# Clocking.net
KiCad netlist of a schematic drawn in Altium Designer
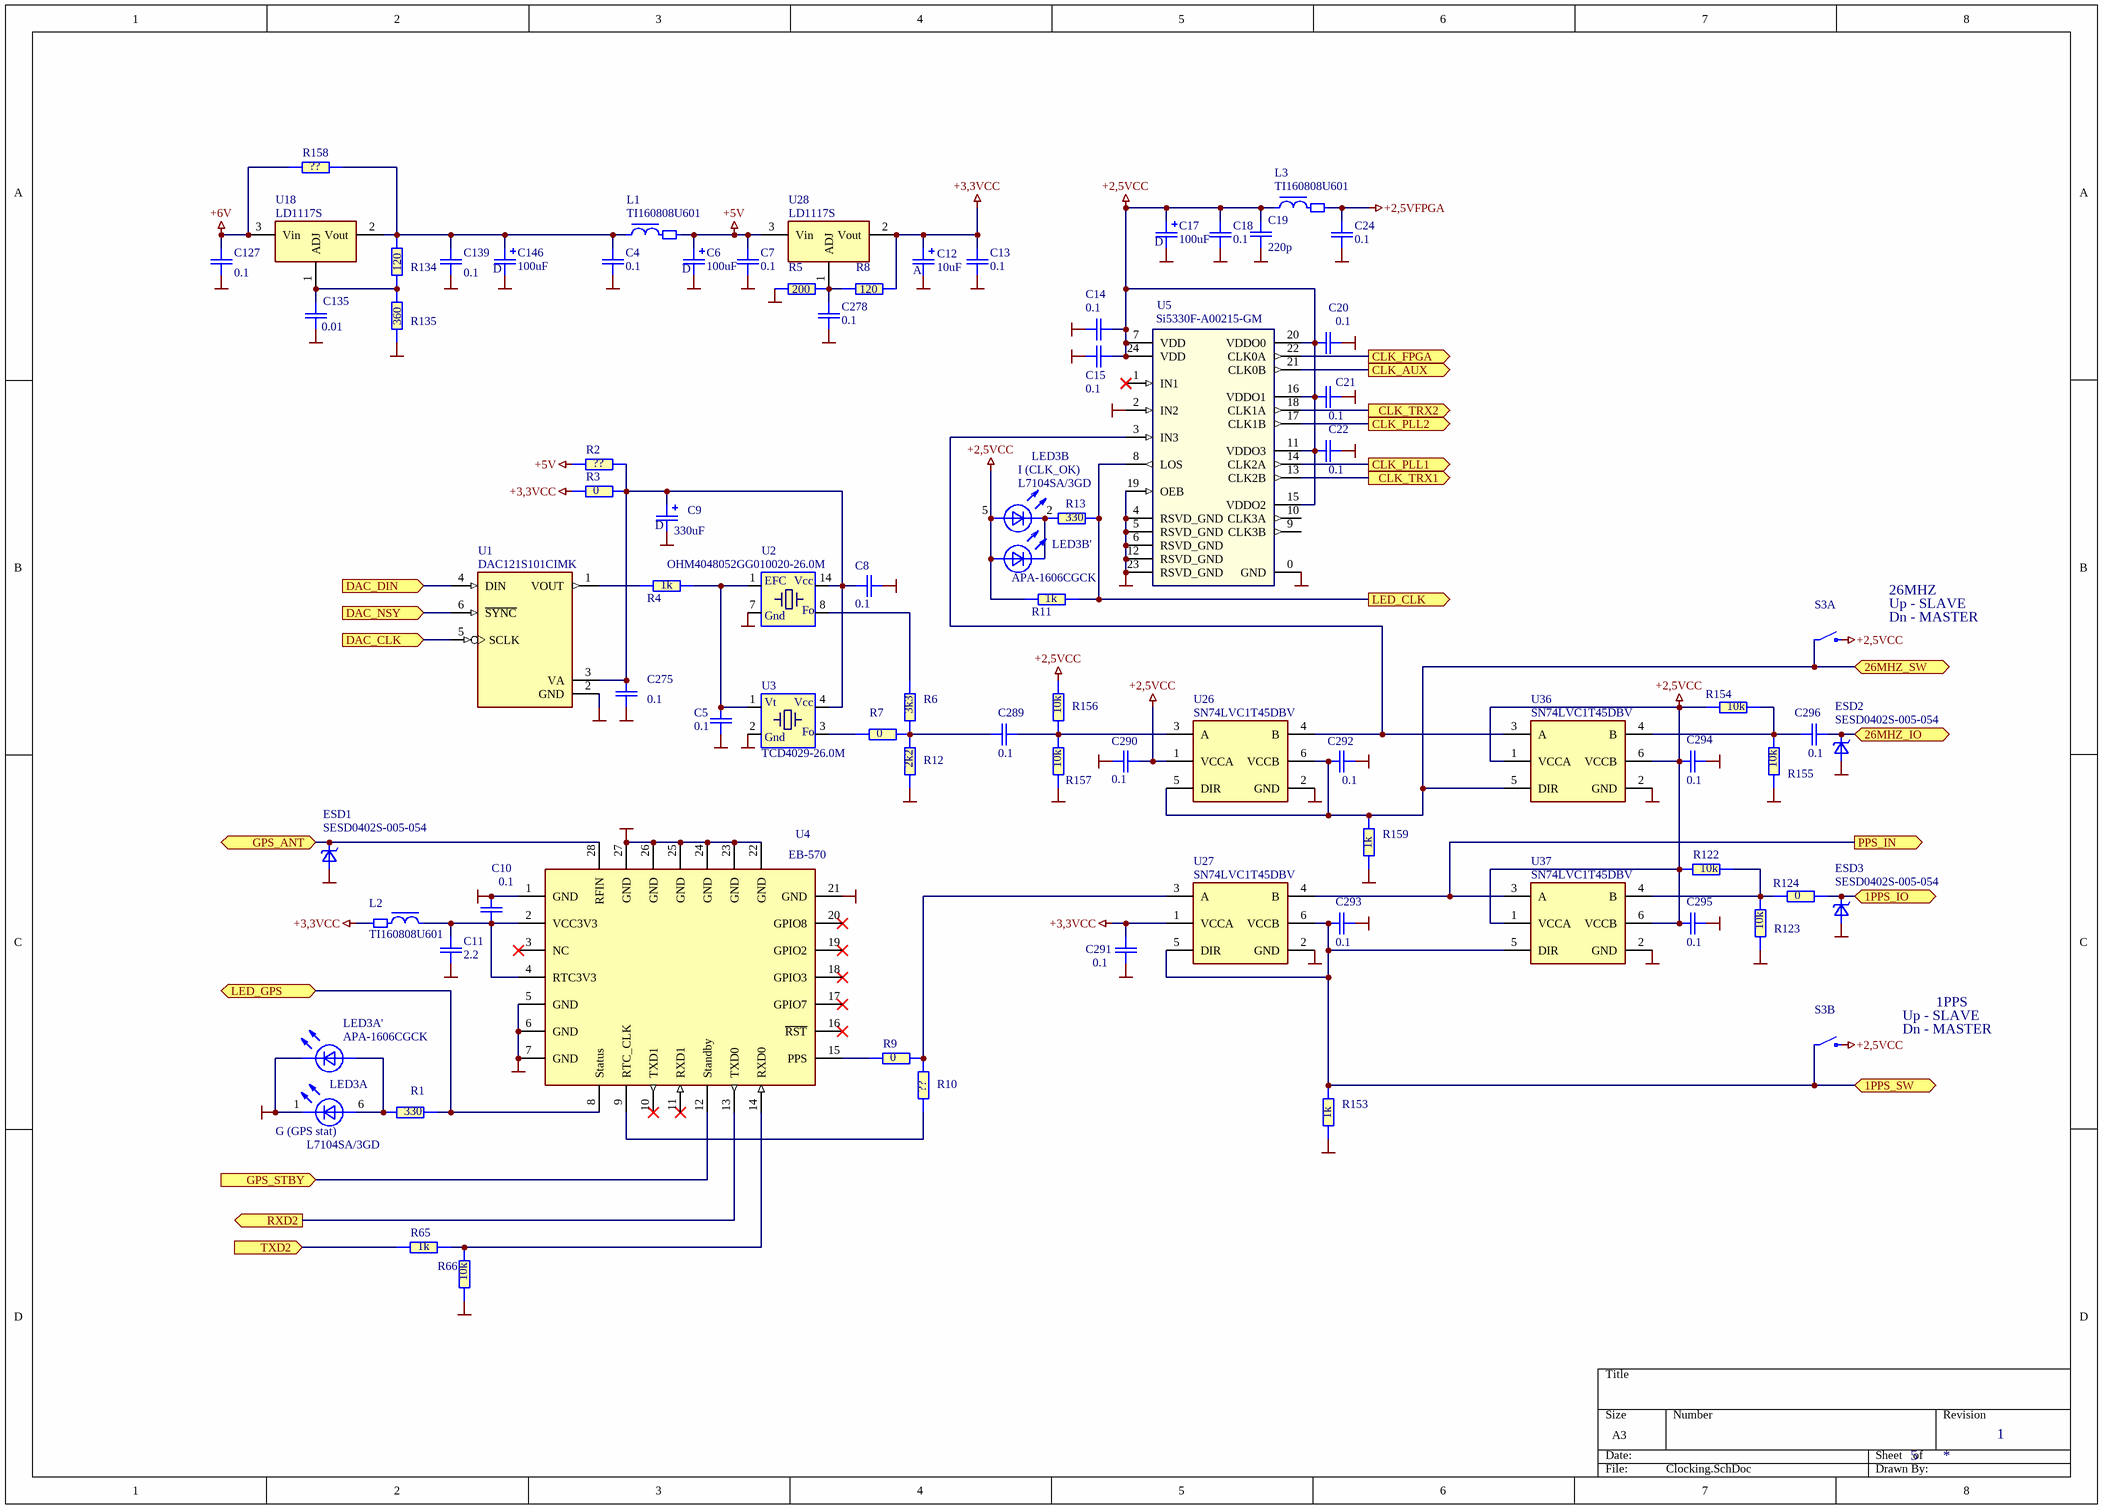
[diagram p0: Clocking.SchDoc]

(export (version "E")
  (design (tool "Eeschema 10.0.6"))
  (components
    (comp (ref "C4")
      (value "0.1")
      (footprint "C0402-Phillips")
      (description "Конденсатор")
      (fields (field (name "MANUFACTURER") "MURATA") (field (name "TOLERANCE") "20%"))
      (libsource (lib "Capacitors") (part "C0402"))
    )
    (comp (ref "C5")
      (value "0.1")
      (footprint "C0402-Phillips")
      (description "Конденсатор")
      (fields (field (name "MANUFACTURER") "MURATA") (field (name "TOLERANCE") "20%"))
      (libsource (lib "Capacitors") (part "C0402"))
    )
    (comp (ref "C6")
      (value "100uF")
      (footprint "cd7343")
      (description "Конденсатор")
      (fields (field (name "MANUFACTURER") "SPRAGUE"))
      (libsource (lib "Capacitors") (part "CD7343"))
    )
    (comp (ref "C7")
      (value "0.1")
      (footprint "C0402-Phillips")
      (description "Конденсатор")
      (fields (field (name "MANUFACTURER") "MURATA") (field (name "TOLERANCE") "20%"))
      (libsource (lib "Capacitors") (part "C0402"))
    )
    (comp (ref "C8")
      (value "0.1")
      (footprint "C0402-Phillips")
      (description "Конденсатор")
      (fields (field (name "MANUFACTURER") "MURATA") (field (name "TOLERANCE") "20%"))
      (libsource (lib "Capacitors") (part "C0402"))
    )
    (comp (ref "C9")
      (value "330uF")
      (footprint "cd7343")
      (description "Конденсатор")
      (fields (field (name "MANUFACTURER") "Kemet"))
      (libsource (lib "altium-import") (part "root_0_CD7343_"))
    )
    (comp (ref "C10")
      (value "0.1")
      (footprint "C0402-Phillips")
      (description "Конденсатор")
      (fields (field (name "MANUFACTURER") "MURATA") (field (name "TOLERANCE") "20%"))
      (libsource (lib "Capacitors") (part "C0402"))
    )
    (comp (ref "C11")
      (value "2.2")
      (footprint "C0402-Phillips")
      (description "Конденсатор")
      (fields (field (name "MANUFACTURER") "MURATA") (field (name "TOLERANCE") "20%"))
      (libsource (lib "Capacitors") (part "C0402"))
    )
    (comp (ref "C12")
      (value "10uF")
      (footprint "CA3216")
      (description "Конденсатор")
      (fields (field (name "MANUFACTURER") "SPRAGUE"))
      (libsource (lib "Capacitors") (part "CA3216"))
    )
    (comp (ref "C13")
      (value "0.1")
      (footprint "C0402-Phillips")
      (description "Конденсатор")
      (fields (field (name "MANUFACTURER") "MURATA") (field (name "TOLERANCE") "20%"))
      (libsource (lib "Capacitors") (part "C0402"))
    )
    (comp (ref "C14")
      (value "0.1")
      (footprint "C0402-Phillips")
      (description "Конденсатор")
      (fields (field (name "MANUFACTURER") "MURATA") (field (name "TOLERANCE") "20%"))
      (libsource (lib "Capacitors") (part "C0402"))
    )
    (comp (ref "C15")
      (value "0.1")
      (footprint "C0402-Phillips")
      (description "Конденсатор")
      (fields (field (name "MANUFACTURER") "MURATA") (field (name "TOLERANCE") "20%"))
      (libsource (lib "Capacitors") (part "C0402"))
    )
    (comp (ref "C17")
      (value "100uF")
      (footprint "cd7343")
      (description "Конденсатор")
      (fields (field (name "MANUFACTURER") "SPRAGUE"))
      (libsource (lib "Capacitors") (part "CD7343"))
    )
    (comp (ref "C18")
      (value "0.1")
      (footprint "C0402-Phillips")
      (description "Конденсатор")
      (fields (field (name "MANUFACTURER") "MURATA") (field (name "TOLERANCE") "20%"))
      (libsource (lib "Capacitors") (part "C0402"))
    )
    (comp (ref "C19")
      (value "220p")
      (footprint "C0603-PHILLIPS")
      (description "Конденсатор")
      (fields (field (name "MANUFACTURER") "MURATA") (field (name "TOLERANCE") "20%"))
      (libsource (lib "Capacitors") (part "C0603"))
    )
    (comp (ref "C20")
      (value "0.1")
      (footprint "C0402-Phillips")
      (description "Конденсатор")
      (fields (field (name "MANUFACTURER") "MURATA") (field (name "TOLERANCE") "20%"))
      (libsource (lib "Capacitors") (part "C0402"))
    )
    (comp (ref "C21")
      (value "0.1")
      (footprint "C0402-Phillips")
      (description "Конденсатор")
      (fields (field (name "MANUFACTURER") "MURATA") (field (name "TOLERANCE") "20%"))
      (libsource (lib "Capacitors") (part "C0402"))
    )
    (comp (ref "C22")
      (value "0.1")
      (footprint "C0402-Phillips")
      (description "Конденсатор")
      (fields (field (name "MANUFACTURER") "MURATA") (field (name "TOLERANCE") "20%"))
      (libsource (lib "Capacitors") (part "C0402"))
    )
    (comp (ref "C24")
      (value "0.1")
      (footprint "C0402-Phillips")
      (description "Конденсатор")
      (fields (field (name "MANUFACTURER") "MURATA") (field (name "TOLERANCE") "20%"))
      (libsource (lib "Capacitors") (part "C0402"))
    )
    (comp (ref "C127")
      (value "0.1")
      (footprint "C0402-Phillips")
      (description "Конденсатор")
      (fields (field (name "MANUFACTURER") "MURATA") (field (name "TOLERANCE") "20%"))
      (libsource (lib "Capacitors") (part "C0402"))
    )
    (comp (ref "C135")
      (value "0.01")
      (footprint "C0402-Phillips")
      (description "Конденсатор")
      (fields (field (name "MANUFACTURER") "MURATA") (field (name "TOLERANCE") "20%"))
      (libsource (lib "Capacitors") (part "C0402"))
    )
    (comp (ref "C139")
      (value "0.1")
      (footprint "C0402-Phillips")
      (description "Конденсатор")
      (fields (field (name "MANUFACTURER") "MURATA") (field (name "TOLERANCE") "20%"))
      (libsource (lib "Capacitors") (part "C0402"))
    )
    (comp (ref "C146")
      (value "100uF")
      (footprint "cd7343")
      (description "Конденсатор")
      (fields (field (name "MANUFACTURER") "SPRAGUE"))
      (libsource (lib "altium-import") (part "root_0_CD7343_"))
    )
    (comp (ref "C275")
      (value "0.1")
      (footprint "C0402-Phillips")
      (description "Конденсатор")
      (fields (field (name "MANUFACTURER") "MURATA") (field (name "TOLERANCE") "20%"))
      (libsource (lib "Capacitors") (part "C0402"))
    )
    (comp (ref "C278")
      (value "0.1")
      (footprint "C0402-Phillips")
      (description "Конденсатор")
      (fields (field (name "MANUFACTURER") "MURATA") (field (name "TOLERANCE") "20%"))
      (libsource (lib "Capacitors") (part "C0402"))
    )
    (comp (ref "C289")
      (value "0.1")
      (footprint "C0402-Phillips")
      (description "Конденсатор")
      (fields (field (name "MANUFACTURER") "MURATA") (field (name "TOLERANCE") "20%"))
      (libsource (lib "Capacitors") (part "C0402"))
    )
    (comp (ref "C290")
      (value "0.1")
      (footprint "C0402-Phillips")
      (description "Конденсатор")
      (fields (field (name "MANUFACTURER") "MURATA") (field (name "TOLERANCE") "20%"))
      (libsource (lib "Capacitors") (part "C0402"))
    )
    (comp (ref "C291")
      (value "0.1")
      (footprint "C0402-Phillips")
      (description "Конденсатор")
      (fields (field (name "MANUFACTURER") "MURATA") (field (name "TOLERANCE") "20%"))
      (libsource (lib "Capacitors") (part "C0402"))
    )
    (comp (ref "C292")
      (value "0.1")
      (footprint "C0402-Phillips")
      (description "Конденсатор")
      (fields (field (name "MANUFACTURER") "MURATA") (field (name "TOLERANCE") "20%"))
      (libsource (lib "Capacitors") (part "C0402"))
    )
    (comp (ref "C293")
      (value "0.1")
      (footprint "C0402-Phillips")
      (description "Конденсатор")
      (fields (field (name "MANUFACTURER") "MURATA") (field (name "TOLERANCE") "20%"))
      (libsource (lib "Capacitors") (part "C0402"))
    )
    (comp (ref "C294")
      (value "0.1")
      (footprint "C0402-Phillips")
      (description "Конденсатор")
      (fields (field (name "MANUFACTURER") "MURATA") (field (name "TOLERANCE") "20%"))
      (libsource (lib "Capacitors") (part "C0402"))
    )
    (comp (ref "C295")
      (value "0.1")
      (footprint "C0402-Phillips")
      (description "Конденсатор")
      (fields (field (name "MANUFACTURER") "MURATA") (field (name "TOLERANCE") "20%"))
      (libsource (lib "Capacitors") (part "C0402"))
    )
    (comp (ref "C296")
      (value "0.1")
      (footprint "C0402-Phillips")
      (description "Конденсатор")
      (fields (field (name "MANUFACTURER") "MURATA") (field (name "TOLERANCE") "20%"))
      (libsource (lib "Capacitors") (part "C0402"))
    )
    (comp (ref "ESD1")
      (value "SESD0402S-005-054")
      (footprint "SESD0402-Phillips")
      (description "ESD diod unidirectional")
      (fields (field (name "MANUFACTURER") "Tyco Electronics Corp"))
      (libsource (lib "Andy") (part "SESD0402S"))
    )
    (comp (ref "ESD2")
      (value "SESD0402S-005-054")
      (footprint "SESD0402-Phillips")
      (description "ESD diod unidirectional")
      (fields (field (name "MANUFACTURER") "Tyco Electronics Corp"))
      (libsource (lib "Andy") (part "SESD0402S"))
    )
    (comp (ref "ESD3")
      (value "SESD0402S-005-054")
      (footprint "SESD0402-Phillips")
      (description "ESD diod unidirectional")
      (fields (field (name "MANUFACTURER") "Tyco Electronics Corp"))
      (libsource (lib "Andy") (part "SESD0402S"))
    )
    (comp (ref "L1")
      (value "TI160808U601")
      (footprint "Andy:Ti160808-Phillips")
      (description "Дроссель ЭМС")
      (fields (field (name "MANUFACTURER") "MURATA"))
      (libsource (lib "altium-import") (part "root_0_TI160808_"))
    )
    (comp (ref "L2")
      (value "TI160808U601")
      (footprint "Andy:Ti160808-Phillips")
      (description "Дроссель ЭМС")
      (fields (field (name "MANUFACTURER") "MURATA"))
      (libsource (lib "altium-import") (part "root_0_mirrored_TI160808_"))
    )
    (comp (ref "L3")
      (value "TI160808U601")
      (footprint "Andy:Ti160808-Phillips")
      (description "Дроссель ЭМС")
      (fields (field (name "MANUFACTURER") "MURATA"))
      (libsource (lib "altium-import") (part "root_0_TI160808_"))
    )
    (comp (ref "LED3")
      (value "L7104SA/3GD")
      (footprint "L-7104SA/3")
      (description "Светодиод")
      (fields (field (name "MANUFACTURER") "KINGBRIGTH"))
      (libsource (lib "Diods") (part "L7104SA/3"))
    )
    (comp (ref "LED3A'")
      (value "APA-1606CGCK")
      (footprint "KPA-1606g")
      (description "Светодиод")
      (fields (field (name "MANUFACTURER") "Kingbright"))
      (libsource (lib "Diods") (part "KPA-1606"))
    )
    (comp (ref "LED3B'")
      (value "APA-1606CGCK")
      (footprint "KPA-1606g")
      (description "Светодиод")
      (fields (field (name "MANUFACTURER") "Kingbright"))
      (libsource (lib "Diods") (part "KPA-1606"))
    )
    (comp (ref "R1")
      (value "330")
      (footprint "R0603-PHILLIPS")
      (description "Резистор")
      (fields (field (name "MANUFACTURER") "YAGEO") (field (name "TOLERANCE") "5%"))
      (libsource (lib "altium-import") (part "root_1_R0603_"))
    )
    (comp (ref "R2")
      (value "??")
      (footprint "R0603-PHILLIPS")
      (description "Резистор")
      (fields (field (name "MANUFACTURER") "YAGEO") (field (name "TOLERANCE") "5%"))
      (libsource (lib "altium-import") (part "root_1_R0603_"))
    )
    (comp (ref "R3")
      (value "0")
      (footprint "R0603-PHILLIPS")
      (description "Резистор")
      (fields (field (name "MANUFACTURER") "YAGEO") (field (name "TOLERANCE") "5%"))
      (libsource (lib "altium-import") (part "root_1_R0603_"))
    )
    (comp (ref "R4")
      (value "1k")
      (footprint "R0603-PHILLIPS")
      (description "Резистор")
      (fields (field (name "MANUFACTURER") "YAGEO") (field (name "TOLERANCE") "5%"))
      (libsource (lib "altium-import") (part "root_1_R0603_"))
    )
    (comp (ref "R5")
      (value "200")
      (footprint "R0603-PHILLIPS")
      (description "Резистор")
      (fields (field (name "MANUFACTURER") "YAGEO") (field (name "TOLERANCE") "5%"))
      (libsource (lib "altium-import") (part "root_1_R0603_"))
    )
    (comp (ref "R6")
      (value "3k3")
      (footprint "R0603-PHILLIPS")
      (description "Резистор")
      (fields (field (name "MANUFACTURER") "YAGEO") (field (name "TOLERANCE") "5%"))
      (libsource (lib "altium-import") (part "root_0_R0603_"))
    )
    (comp (ref "R7")
      (value "0")
      (footprint "R0603-PHILLIPS")
      (description "Резистор")
      (fields (field (name "MANUFACTURER") "YAGEO") (field (name "TOLERANCE") "5%"))
      (libsource (lib "altium-import") (part "root_1_R0603_"))
    )
    (comp (ref "R8")
      (value "120")
      (footprint "R0603-PHILLIPS")
      (description "Резистор")
      (fields (field (name "MANUFACTURER") "YAGEO") (field (name "TOLERANCE") "5%"))
      (libsource (lib "altium-import") (part "root_1_R0603_"))
    )
    (comp (ref "R9")
      (value "0")
      (footprint "R0603-PHILLIPS")
      (description "Резистор")
      (fields (field (name "MANUFACTURER") "YAGEO") (field (name "TOLERANCE") "5%"))
      (libsource (lib "altium-import") (part "root_1_R0603_"))
    )
    (comp (ref "R10")
      (value "??")
      (footprint "R0603-PHILLIPS")
      (description "Резистор")
      (fields (field (name "MANUFACTURER") "YAGEO") (field (name "TOLERANCE") "5%"))
      (libsource (lib "altium-import") (part "root_2_R0603_"))
    )
    (comp (ref "R11")
      (value "1k")
      (footprint "R0603-PHILLIPS")
      (description "Резистор")
      (fields (field (name "MANUFACTURER") "YAGEO") (field (name "TOLERANCE") "5%"))
      (libsource (lib "altium-import") (part "root_1_R0603_"))
    )
    (comp (ref "R12")
      (value "2k2")
      (footprint "R0603-PHILLIPS")
      (description "Резистор")
      (fields (field (name "MANUFACTURER") "YAGEO") (field (name "TOLERANCE") "5%"))
      (libsource (lib "altium-import") (part "root_2_R0603_"))
    )
    (comp (ref "R13")
      (value "330")
      (footprint "R0603-PHILLIPS")
      (description "Резистор")
      (fields (field (name "MANUFACTURER") "YAGEO") (field (name "TOLERANCE") "5%"))
      (libsource (lib "altium-import") (part "root_1_R0603_"))
    )
    (comp (ref "R65")
      (value "1k")
      (footprint "R0603-PHILLIPS")
      (description "Резистор")
      (fields (field (name "MANUFACTURER") "YAGEO") (field (name "TOLERANCE") "5%"))
      (libsource (lib "altium-import") (part "root_1_R0603_"))
    )
    (comp (ref "R66")
      (value "10k")
      (footprint "R0603-PHILLIPS")
      (description "Резистор")
      (fields (field (name "MANUFACTURER") "YAGEO") (field (name "TOLERANCE") "5%"))
      (libsource (lib "altium-import") (part "root_2_R0603_"))
    )
    (comp (ref "R122")
      (value "10k")
      (footprint "R0603-PHILLIPS")
      (description "Резистор")
      (fields (field (name "MANUFACTURER") "YAGEO") (field (name "TOLERANCE") "5%"))
      (libsource (lib "altium-import") (part "root_3_R0603_"))
    )
    (comp (ref "R123")
      (value "10k")
      (footprint "R0603-PHILLIPS")
      (description "Резистор")
      (fields (field (name "MANUFACTURER") "YAGEO") (field (name "TOLERANCE") "5%"))
      (libsource (lib "altium-import") (part "root_0_R0603_"))
    )
    (comp (ref "R124")
      (value "0")
      (footprint "R0603-PHILLIPS")
      (description "Резистор")
      (fields (field (name "MANUFACTURER") "YAGEO") (field (name "TOLERANCE") "5%"))
      (libsource (lib "altium-import") (part "root_3_R0603_"))
    )
    (comp (ref "R134")
      (value "120")
      (footprint "R0603-PHILLIPS")
      (description "Резистор")
      (fields (field (name "MANUFACTURER") "YAGEO") (field (name "TOLERANCE") "5%"))
      (libsource (lib "altium-import") (part "root_0_R0603_"))
    )
    (comp (ref "R135")
      (value "360")
      (footprint "R0603-PHILLIPS")
      (description "Резистор")
      (fields (field (name "MANUFACTURER") "YAGEO") (field (name "TOLERANCE") "5%"))
      (libsource (lib "altium-import") (part "root_0_R0603_"))
    )
    (comp (ref "R153")
      (value "1k")
      (footprint "R0603-PHILLIPS")
      (description "Резистор")
      (fields (field (name "MANUFACTURER") "YAGEO") (field (name "TOLERANCE") "5%"))
      (libsource (lib "altium-import") (part "root_2_R0603_"))
    )
    (comp (ref "R154")
      (value "10k")
      (footprint "R0603-PHILLIPS")
      (description "Резистор")
      (fields (field (name "MANUFACTURER") "YAGEO") (field (name "TOLERANCE") "5%"))
      (libsource (lib "altium-import") (part "root_3_R0603_"))
    )
    (comp (ref "R155")
      (value "10k")
      (footprint "R0603-PHILLIPS")
      (description "Резистор")
      (fields (field (name "MANUFACTURER") "YAGEO") (field (name "TOLERANCE") "5%"))
      (libsource (lib "altium-import") (part "root_0_R0603_"))
    )
    (comp (ref "R156")
      (value "10k")
      (footprint "R0603-PHILLIPS")
      (description "Резистор")
      (fields (field (name "MANUFACTURER") "YAGEO") (field (name "TOLERANCE") "5%"))
      (libsource (lib "altium-import") (part "root_0_R0603_"))
    )
    (comp (ref "R157")
      (value "10k")
      (footprint "R0603-PHILLIPS")
      (description "Резистор")
      (fields (field (name "MANUFACTURER") "YAGEO") (field (name "TOLERANCE") "5%"))
      (libsource (lib "altium-import") (part "root_0_R0603_"))
    )
    (comp (ref "R158")
      (value "??")
      (footprint "R0603-PHILLIPS")
      (description "Резистор")
      (fields (field (name "MANUFACTURER") "YAGEO") (field (name "TOLERANCE") "5%"))
      (libsource (lib "altium-import") (part "root_1_R0603_"))
    )
    (comp (ref "R159")
      (value "1k")
      (footprint "R0603-PHILLIPS")
      (description "Резистор")
      (fields (field (name "MANUFACTURER") "YAGEO") (field (name "TOLERANCE") "5%"))
      (libsource (lib "altium-import") (part "root_2_R0603_"))
    )
    (comp (ref "S3")
      (value "CHP-021A")
      (footprint "CHP-02xA")
      (description "Switch 2pos Piano SMD right angle")
      (fields (field (name "MANUFACTURER") "Copal Electronics"))
      (libsource (lib "Andy") (part "CHP-021A"))
    )
    (comp (ref "U1")
      (value "DAC121S101CIMK")
      (footprint "SOT-23-6")
      (description "Микросхема")
      (fields (field (name "MANUFACTURER") "National Semiconductor"))
      (libsource (lib "altium-import") (part "root_0_DAC121S101CIMK_"))
    )
    (comp (ref "U2")
      (value "OHM4048052GG010020-26.0M")
      (footprint "Andy:DIL14-20x13,2")
      (description "OCVCXO")
      (fields (field (name "MANUFACTURER") "Pletronics"))
      (libsource (lib "altium-import") (part "root_0_OCVCXO_"))
    )
    (comp (ref "U3")
      (value "TCD4029-26.0M")
      (footprint "Andy:TCXO5X3")
      (description "TCVCXO")
      (fields (field (name "MANUFACTURER") "Pletronics"))
      (libsource (lib "Andy") (part "TCVCXO_5X3"))
    )
    (comp (ref "U4")
      (value "EB-570")
      (footprint "EB-570")
      (description "Микросхема")
      (fields (field (name "MANUFACTURER") "Transystem Inc."))
      (libsource (lib "Andy") (part "EB-570"))
    )
    (comp (ref "U5")
      (value "Si5330F-A00215-GM")
      (footprint "QFN-24(4x4/0/5mm) with Pad")
      (description "Микросхема")
      (fields (field (name "MANUFACTURER") "Silicon Laboratoryes"))
      (libsource (lib "altium-import") (part "root_0_SI5330_"))
    )
    (comp (ref "U18")
      (value "LD1117S")
      (footprint "Foot3-4pins:SOT-223-1")
      (description "Микросхема")
      (fields (field (name "MANUFACTURER") "STMicro"))
      (libsource (lib "altium-import") (part "root_0_LD1117ADJ_"))
    )
    (comp (ref "U26")
      (value "SN74LVC1T45DBV")
      (footprint "SOT-23-6-min")
      (description "Микросхема")
      (fields (field (name "MANUFACTURER") "TI"))
      (libsource (lib "MicroCircuitsM-Z") (part "SN74LVC1T45DBV"))
    )
    (comp (ref "U27")
      (value "SN74LVC1T45DBV")
      (footprint "SOT-23-6-min")
      (description "Микросхема")
      (fields (field (name "MANUFACTURER") "TI"))
      (libsource (lib "MicroCircuitsM-Z") (part "SN74LVC1T45DBV"))
    )
    (comp (ref "U28")
      (value "LD1117S")
      (footprint "Foot3-4pins:SOT-223-1")
      (description "Микросхема")
      (fields (field (name "MANUFACTURER") "STMicro"))
      (libsource (lib "altium-import") (part "root_0_LD1117ADJ_"))
    )
    (comp (ref "U36")
      (value "SN74LVC1T45DBV")
      (footprint "SOT-23-6-min")
      (description "Микросхема")
      (fields (field (name "MANUFACTURER") "TI"))
      (libsource (lib "MicroCircuitsM-Z") (part "SN74LVC1T45DBV"))
    )
    (comp (ref "U37")
      (value "SN74LVC1T45DBV")
      (footprint "SOT-23-6-min")
      (description "Микросхема")
      (fields (field (name "MANUFACTURER") "TI"))
      (libsource (lib "MicroCircuitsM-Z") (part "SN74LVC1T45DBV"))
    )
  )
  (nets
    (net (code "1") (name "+2,5VCC") (class "Default")
      (node (ref "C14") (pin "2") (pinfunction "2_2") (pintype "passive"))
      (node (ref "C15") (pin "2") (pinfunction "2_2") (pintype "passive"))
      (node (ref "C17") (pin "1") (pinfunction "+_1") (pintype "passive"))
      (node (ref "C18") (pin "1") (pinfunction "1_1") (pintype "passive"))
      (node (ref "C19") (pin "1") (pinfunction "1_1") (pintype "passive"))
      (node (ref "C20") (pin "1") (pinfunction "1_1") (pintype "passive"))
      (node (ref "C21") (pin "1") (pinfunction "1_1") (pintype "passive"))
      (node (ref "C22") (pin "1") (pinfunction "1_1") (pintype "passive"))
      (node (ref "C290") (pin "1") (pinfunction "1_1") (pintype "passive"))
      (node (ref "C294") (pin "2") (pinfunction "2_2") (pintype "passive"))
      (node (ref "C295") (pin "2") (pinfunction "2_2") (pintype "passive"))
      (node (ref "L3") (pin "1") (pinfunction "1_1") (pintype "passive"))
      (node (ref "LED3") (pin "5") (pinfunction "A2_5") (pintype "passive"))
      (node (ref "LED3B'") (pin "2") (pinfunction "A_2") (pintype "passive"))
      (node (ref "R11") (pin "1") (pinfunction "1_1") (pintype "passive"))
      (node (ref "R122") (pin "2") (pinfunction "2_2") (pintype "passive"))
      (node (ref "R154") (pin "2") (pinfunction "2_2") (pintype "passive"))
      (node (ref "R156") (pin "1") (pinfunction "1_1") (pintype "passive"))
      (node (ref "S3") (pin "3") (pinfunction "3_3") (pintype "passive"))
      (node (ref "S3") (pin "4") (pinfunction "4_4") (pintype "passive"))
      (node (ref "U26") (pin "1") (pinfunction "VCCA_1") (pintype "power_in"))
      (node (ref "U36") (pin "1") (pinfunction "VCCA_1") (pintype "power_in"))
      (node (ref "U36") (pin "6") (pinfunction "VCCB_6") (pintype "power_in"))
      (node (ref "U37") (pin "1") (pinfunction "VCCA_1") (pintype "power_in"))
      (node (ref "U37") (pin "6") (pinfunction "VCCB_6") (pintype "power_in"))
      (node (ref "U5") (pin "11") (pinfunction "VDDO3_11") (pintype "power_in"))
      (node (ref "U5") (pin "15") (pinfunction "VDDO2_15") (pintype "power_in"))
      (node (ref "U5") (pin "16") (pinfunction "VDDO1_16") (pintype "power_in"))
      (node (ref "U5") (pin "20") (pinfunction "VDDO0_20") (pintype "power_in"))
      (node (ref "U5") (pin "24") (pinfunction "VDD_24") (pintype "power_in"))
      (node (ref "U5") (pin "7") (pinfunction "VDD_7") (pintype "power_in"))
    )
    (net (code "2") (name "+2,5VFPGA") (class "Default")
      (node (ref "C24") (pin "1") (pinfunction "1_1") (pintype "passive"))
      (node (ref "L3") (pin "2") (pinfunction "2_2") (pintype "passive"))
    )
    (net (code "3") (name "+3,3VCC") (class "Default")
      (node (ref "C12") (pin "1") (pinfunction "+_1") (pintype "passive"))
      (node (ref "C13") (pin "1") (pinfunction "1_1") (pintype "passive"))
      (node (ref "C291") (pin "1") (pinfunction "1_1") (pintype "passive"))
      (node (ref "L2") (pin "2") (pinfunction "2_2") (pintype "passive"))
      (node (ref "R3") (pin "1") (pinfunction "1_1") (pintype "passive"))
      (node (ref "R8") (pin "2") (pinfunction "2_2") (pintype "passive"))
      (node (ref "U27") (pin "1") (pinfunction "VCCA_1") (pintype "power_in"))
      (node (ref "U28") (pin "2") (pinfunction "Vout_2") (pintype "passive"))
    )
    (net (code "4") (name "+5V") (class "Default")
      (node (ref "C6") (pin "1") (pinfunction "+_1") (pintype "passive"))
      (node (ref "C7") (pin "1") (pinfunction "1_1") (pintype "passive"))
      (node (ref "L1") (pin "2") (pinfunction "2_2") (pintype "passive"))
      (node (ref "R2") (pin "1") (pinfunction "1_1") (pintype "passive"))
      (node (ref "U28") (pin "3") (pinfunction "Vin_3") (pintype "passive"))
    )
    (net (code "5") (name "+6V") (class "Default")
      (node (ref "C127") (pin "1") (pinfunction "1_1") (pintype "passive"))
      (node (ref "R158") (pin "1") (pinfunction "1_1") (pintype "passive"))
      (node (ref "U18") (pin "3") (pinfunction "Vin_3") (pintype "passive"))
    )
    (net (code "6") (name "/1PPS_IO") (class "Default")
      (node (ref "ESD3") (pin "1") (pinfunction "K_1") (pintype "passive"))
      (node (ref "R124") (pin "1") (pinfunction "1_1") (pintype "passive"))
    )
    (net (code "7") (name "/1PPS_SW") (class "Default")
      (node (ref "C293") (pin "2") (pinfunction "2_2") (pintype "passive"))
      (node (ref "R153") (pin "2") (pinfunction "2_2") (pintype "passive"))
      (node (ref "S3") (pin "2") (pinfunction "2_2") (pintype "passive"))
      (node (ref "U27") (pin "5") (pinfunction "DIR_5") (pintype "passive"))
      (node (ref "U27") (pin "6") (pinfunction "VCCB_6") (pintype "power_in"))
      (node (ref "U37") (pin "5") (pinfunction "DIR_5") (pintype "passive"))
    )
    (net (code "8") (name "/26MHZ_IO") (class "Default")
      (node (ref "C296") (pin "1") (pinfunction "1_1") (pintype "passive"))
      (node (ref "ESD2") (pin "1") (pinfunction "K_1") (pintype "passive"))
    )
    (net (code "9") (name "/26MHZ_SW") (class "Default")
      (node (ref "C292") (pin "2") (pinfunction "2_2") (pintype "passive"))
      (node (ref "R159") (pin "2") (pinfunction "2_2") (pintype "passive"))
      (node (ref "S3") (pin "1") (pinfunction "1_1") (pintype "passive"))
      (node (ref "U26") (pin "5") (pinfunction "DIR_5") (pintype "passive"))
      (node (ref "U26") (pin "6") (pinfunction "VCCB_6") (pintype "power_in"))
      (node (ref "U36") (pin "5") (pinfunction "DIR_5") (pintype "passive"))
    )
    (net (code "10") (name "/CLK_AUX") (class "Default")
      (node (ref "U5") (pin "21") (pinfunction "CLK0B_21") (pintype "output"))
    )
    (net (code "11") (name "/CLK_FPGA") (class "Default")
      (node (ref "U5") (pin "22") (pinfunction "CLK0A_22") (pintype "output"))
    )
    (net (code "12") (name "/CLK_PLL1") (class "Default")
      (node (ref "U5") (pin "14") (pinfunction "CLK2A_14") (pintype "output"))
    )
    (net (code "13") (name "/CLK_PLL2") (class "Default")
      (node (ref "U5") (pin "17") (pinfunction "CLK1B_17") (pintype "output"))
    )
    (net (code "14") (name "/CLK_TRX1") (class "Default")
      (node (ref "U5") (pin "13") (pinfunction "CLK2B_13") (pintype "output"))
    )
    (net (code "15") (name "/CLK_TRX2") (class "Default")
      (node (ref "U5") (pin "18") (pinfunction "CLK1A_18") (pintype "output"))
    )
    (net (code "16") (name "/DAC_CLK") (class "Default")
      (node (ref "U1") (pin "5") (pinfunction "SCLK_5") (pintype "input"))
    )
    (net (code "17") (name "/DAC_DIN") (class "Default")
      (node (ref "U1") (pin "4") (pinfunction "DIN_4") (pintype "input"))
    )
    (net (code "18") (name "/DAC_NSY") (class "Default")
      (node (ref "U1") (pin "6") (pinfunction "~{SYNC}_6") (pintype "input"))
    )
    (net (code "19") (name "/GPS_ANT") (class "Default")
      (node (ref "ESD1") (pin "1") (pinfunction "K_1") (pintype "passive"))
      (node (ref "U4") (pin "28") (pinfunction "RFIN_28") (pintype "passive"))
    )
    (net (code "20") (name "/GPS_STBY") (class "Default")
      (node (ref "U4") (pin "12") (pinfunction "Standby_12") (pintype "passive"))
    )
    (net (code "21") (name "/LED_CLK") (class "Default")
      (node (ref "R11") (pin "2") (pinfunction "2_2") (pintype "passive"))
      (node (ref "R13") (pin "2") (pinfunction "2_2") (pintype "passive"))
      (node (ref "U5") (pin "8") (pinfunction "LOS_8") (pintype "output"))
    )
    (net (code "22") (name "/LED_GPS") (class "Default")
      (node (ref "R1") (pin "2") (pinfunction "2_2") (pintype "passive"))
      (node (ref "U4") (pin "8") (pinfunction "Status_8") (pintype "passive"))
    )
    (net (code "23") (name "/PPS_IN") (class "Default")
      (node (ref "U27") (pin "4") (pinfunction "B_4") (pintype "passive"))
      (node (ref "U37") (pin "3") (pinfunction "A_3") (pintype "passive"))
    )
    (net (code "24") (name "/RXD2") (class "Default")
      (node (ref "U4") (pin "13") (pinfunction "TXD0_13") (pintype "output"))
    )
    (net (code "25") (name "/TXD2") (class "Default")
      (node (ref "R65") (pin "1") (pinfunction "1_1") (pintype "passive"))
    )
    (net (code "26") (name "GND") (class "Default")
      (node (ref "C10") (pin "2") (pinfunction "2_2") (pintype "passive"))
      (node (ref "C11") (pin "2") (pinfunction "2_2") (pintype "passive"))
      (node (ref "C12") (pin "2") (pinfunction "-_2") (pintype "passive"))
      (node (ref "C127") (pin "2") (pinfunction "2_2") (pintype "passive"))
      (node (ref "C13") (pin "2") (pinfunction "2_2") (pintype "passive"))
      (node (ref "C135") (pin "2") (pinfunction "2_2") (pintype "passive"))
      (node (ref "C139") (pin "2") (pinfunction "2_2") (pintype "passive"))
      (node (ref "C14") (pin "1") (pinfunction "1_1") (pintype "passive"))
      (node (ref "C146") (pin "2") (pinfunction "-_2") (pintype "passive"))
      (node (ref "C15") (pin "1") (pinfunction "1_1") (pintype "passive"))
      (node (ref "C17") (pin "2") (pinfunction "-_2") (pintype "passive"))
      (node (ref "C18") (pin "2") (pinfunction "2_2") (pintype "passive"))
      (node (ref "C19") (pin "2") (pinfunction "2_2") (pintype "passive"))
      (node (ref "C20") (pin "2") (pinfunction "2_2") (pintype "passive"))
      (node (ref "C21") (pin "2") (pinfunction "2_2") (pintype "passive"))
      (node (ref "C22") (pin "2") (pinfunction "2_2") (pintype "passive"))
      (node (ref "C24") (pin "2") (pinfunction "2_2") (pintype "passive"))
      (node (ref "C275") (pin "1") (pinfunction "1_1") (pintype "passive"))
      (node (ref "C278") (pin "2") (pinfunction "2_2") (pintype "passive"))
      (node (ref "C290") (pin "2") (pinfunction "2_2") (pintype "passive"))
      (node (ref "C291") (pin "2") (pinfunction "2_2") (pintype "passive"))
      (node (ref "C292") (pin "1") (pinfunction "1_1") (pintype "passive"))
      (node (ref "C293") (pin "1") (pinfunction "1_1") (pintype "passive"))
      (node (ref "C294") (pin "1") (pinfunction "1_1") (pintype "passive"))
      (node (ref "C295") (pin "1") (pinfunction "1_1") (pintype "passive"))
      (node (ref "C4") (pin "2") (pinfunction "2_2") (pintype "passive"))
      (node (ref "C5") (pin "1") (pinfunction "1_1") (pintype "passive"))
      (node (ref "C6") (pin "2") (pinfunction "-_2") (pintype "passive"))
      (node (ref "C7") (pin "2") (pinfunction "2_2") (pintype "passive"))
      (node (ref "C8") (pin "2") (pinfunction "2_2") (pintype "passive"))
      (node (ref "C9") (pin "2") (pinfunction "-_2") (pintype "passive"))
      (node (ref "ESD1") (pin "2") (pinfunction "A_2") (pintype "passive"))
      (node (ref "ESD2") (pin "2") (pinfunction "A_2") (pintype "passive"))
      (node (ref "ESD3") (pin "2") (pinfunction "A_2") (pintype "passive"))
      (node (ref "LED3") (pin "1") (pinfunction "K1_1") (pintype "passive"))
      (node (ref "LED3A'") (pin "1") (pinfunction "K_1") (pintype "passive"))
      (node (ref "R12") (pin "1") (pinfunction "1_1") (pintype "passive"))
      (node (ref "R123") (pin "2") (pinfunction "2_2") (pintype "passive"))
      (node (ref "R135") (pin "2") (pinfunction "2_2") (pintype "passive"))
      (node (ref "R153") (pin "1") (pinfunction "1_1") (pintype "passive"))
      (node (ref "R155") (pin "2") (pinfunction "2_2") (pintype "passive"))
      (node (ref "R157") (pin "2") (pinfunction "2_2") (pintype "passive"))
      (node (ref "R159") (pin "1") (pinfunction "1_1") (pintype "passive"))
      (node (ref "R5") (pin "1") (pinfunction "1_1") (pintype "passive"))
      (node (ref "R66") (pin "1") (pinfunction "1_1") (pintype "passive"))
      (node (ref "U1") (pin "2") (pinfunction "GND_2") (pintype "power_in"))
      (node (ref "U2") (pin "7") (pinfunction "GND_7") (pintype "passive"))
      (node (ref "U26") (pin "2") (pinfunction "GND_2") (pintype "power_in"))
      (node (ref "U27") (pin "2") (pinfunction "GND_2") (pintype "power_in"))
      (node (ref "U3") (pin "2") (pinfunction "GND_2") (pintype "passive"))
      (node (ref "U36") (pin "2") (pinfunction "GND_2") (pintype "power_in"))
      (node (ref "U37") (pin "2") (pinfunction "GND_2") (pintype "power_in"))
      (node (ref "U4") (pin "1") (pinfunction "GND_1") (pintype "power_in"))
      (node (ref "U4") (pin "21") (pinfunction "GND_21") (pintype "power_in"))
      (node (ref "U4") (pin "22") (pinfunction "GND_22") (pintype "power_in"))
      (node (ref "U4") (pin "23") (pinfunction "GND_23") (pintype "power_in"))
      (node (ref "U4") (pin "24") (pinfunction "GND_24") (pintype "power_in"))
      (node (ref "U4") (pin "25") (pinfunction "GND_25") (pintype "power_in"))
      (node (ref "U4") (pin "26") (pinfunction "GND_26") (pintype "power_in"))
      (node (ref "U4") (pin "27") (pinfunction "GND_27") (pintype "power_in"))
      (node (ref "U4") (pin "5") (pinfunction "GND_5") (pintype "power_in"))
      (node (ref "U4") (pin "6") (pinfunction "GND_6") (pintype "power_in"))
      (node (ref "U4") (pin "7") (pinfunction "GND_7") (pintype "power_in"))
      (node (ref "U5") (pin "0") (pinfunction "GND_0") (pintype "power_in"))
      (node (ref "U5") (pin "12") (pinfunction "RSVD_GND_12") (pintype "power_in"))
      (node (ref "U5") (pin "19") (pinfunction "OEB_19") (pintype "input"))
      (node (ref "U5") (pin "2") (pinfunction "IN2_2") (pintype "input"))
      (node (ref "U5") (pin "23") (pinfunction "RSVD_GND_23") (pintype "power_in"))
      (node (ref "U5") (pin "4") (pinfunction "RSVD_GND_4") (pintype "power_in"))
      (node (ref "U5") (pin "5") (pinfunction "RSVD_GND_5") (pintype "power_in"))
      (node (ref "U5") (pin "6") (pinfunction "RSVD_GND_6") (pintype "power_in"))
    )
    (net (code "27") (name "Net-(C9-+)") (class "Default")
      (node (ref "C275") (pin "2") (pinfunction "2_2") (pintype "passive"))
      (node (ref "C8") (pin "1") (pinfunction "1_1") (pintype "passive"))
      (node (ref "C9") (pin "1") (pinfunction "+_1") (pintype "passive"))
      (node (ref "R2") (pin "2") (pinfunction "2_2") (pintype "passive"))
      (node (ref "R3") (pin "2") (pinfunction "2_2") (pintype "passive"))
      (node (ref "U1") (pin "3") (pinfunction "VA_3") (pintype "power_in"))
      (node (ref "U2") (pin "14") (pinfunction "VCC_14") (pintype "power_in"))
      (node (ref "U3") (pin "4") (pinfunction "VCC_4") (pintype "power_in"))
    )
    (net (code "28") (name "Net-(C146-+)") (class "Default")
      (node (ref "C139") (pin "1") (pinfunction "1_1") (pintype "passive"))
      (node (ref "C146") (pin "1") (pinfunction "+_1") (pintype "passive"))
      (node (ref "C4") (pin "1") (pinfunction "1_1") (pintype "passive"))
      (node (ref "L1") (pin "1") (pinfunction "1_1") (pintype "passive"))
      (node (ref "R134") (pin "1") (pinfunction "1_1") (pintype "passive"))
      (node (ref "R158") (pin "2") (pinfunction "2_2") (pintype "passive"))
      (node (ref "U18") (pin "2") (pinfunction "Vout_2") (pintype "passive"))
    )
    (net (code "29") (name "Net-(C289-Pad2)") (class "Default")
      (node (ref "C289") (pin "2") (pinfunction "2_2") (pintype "passive"))
      (node (ref "R12") (pin "2") (pinfunction "2_2") (pintype "passive"))
      (node (ref "R6") (pin "2") (pinfunction "2_2") (pintype "passive"))
      (node (ref "R7") (pin "2") (pinfunction "2_2") (pintype "passive"))
    )
    (net (code "30") (name "Net-(LED3A'-A)") (class "Default")
      (node (ref "LED3") (pin "6") (pinfunction "A1_6") (pintype "passive"))
      (node (ref "LED3A'") (pin "2") (pinfunction "A_2") (pintype "passive"))
      (node (ref "R1") (pin "1") (pinfunction "1_1") (pintype "passive"))
    )
    (net (code "31") (name "Net-(LED3B'-K)") (class "Default")
      (node (ref "LED3") (pin "2") (pinfunction "K2_2") (pintype "passive"))
      (node (ref "LED3B'") (pin "1") (pinfunction "K_1") (pintype "passive"))
      (node (ref "R13") (pin "1") (pinfunction "1_1") (pintype "passive"))
    )
    (net (code "32") (name "Net-(U1-VOUT)") (class "Default")
      (node (ref "R4") (pin "1") (pinfunction "1_1") (pintype "passive"))
      (node (ref "U1") (pin "1") (pinfunction "VOUT_1") (pintype "output"))
    )
    (net (code "33") (name "Net-(U2-EFC)") (class "Default")
      (node (ref "C5") (pin "2") (pinfunction "2_2") (pintype "passive"))
      (node (ref "R4") (pin "2") (pinfunction "2_2") (pintype "passive"))
      (node (ref "U2") (pin "1") (pinfunction "EFC_1") (pintype "passive"))
      (node (ref "U3") (pin "1") (pinfunction "Vtune_1") (pintype "passive"))
    )
    (net (code "34") (name "Net-(U2-Fo)") (class "Default")
      (node (ref "R6") (pin "1") (pinfunction "1_1") (pintype "passive"))
      (node (ref "U2") (pin "8") (pinfunction "Fo_8") (pintype "passive"))
    )
    (net (code "35") (name "Net-(U3-Fo)") (class "Default")
      (node (ref "R7") (pin "1") (pinfunction "1_1") (pintype "passive"))
      (node (ref "U3") (pin "3") (pinfunction "Fo_3") (pintype "passive"))
    )
    (net (code "36") (name "Net-(U4-PPS)") (class "Default")
      (node (ref "R9") (pin "1") (pinfunction "1_1") (pintype "passive"))
      (node (ref "U4") (pin "15") (pinfunction "PPS_15") (pintype "passive"))
    )
    (net (code "37") (name "Net-(U4-RTC3V3)") (class "Default")
      (node (ref "C10") (pin "1") (pinfunction "1_1") (pintype "passive"))
      (node (ref "C11") (pin "1") (pinfunction "1_1") (pintype "passive"))
      (node (ref "L2") (pin "1") (pinfunction "1_1") (pintype "passive"))
      (node (ref "U4") (pin "2") (pinfunction "VCC3V3_2") (pintype "passive"))
      (node (ref "U4") (pin "4") (pinfunction "RTC3V3_4") (pintype "passive"))
    )
    (net (code "38") (name "Net-(U4-RTC_CLK)") (class "Default")
      (node (ref "R10") (pin "1") (pinfunction "1_1") (pintype "passive"))
      (node (ref "U4") (pin "9") (pinfunction "RTC_CLK_9") (pintype "passive"))
    )
    (net (code "39") (name "Net-(U4-RXD0)") (class "Default")
      (node (ref "R65") (pin "2") (pinfunction "2_2") (pintype "passive"))
      (node (ref "R66") (pin "2") (pinfunction "2_2") (pintype "passive"))
      (node (ref "U4") (pin "14") (pinfunction "RXD0_14") (pintype "input"))
    )
    (net (code "40") (name "Net-(U18-ADJ)") (class "Default")
      (node (ref "C135") (pin "1") (pinfunction "1_1") (pintype "passive"))
      (node (ref "R134") (pin "2") (pinfunction "2_2") (pintype "passive"))
      (node (ref "R135") (pin "1") (pinfunction "1_1") (pintype "passive"))
      (node (ref "U18") (pin "1") (pinfunction "ADJ_1") (pintype "passive"))
    )
    (net (code "41") (name "Net-(U26-A)") (class "Default")
      (node (ref "C289") (pin "1") (pinfunction "1_1") (pintype "passive"))
      (node (ref "R156") (pin "2") (pinfunction "2_2") (pintype "passive"))
      (node (ref "R157") (pin "1") (pinfunction "1_1") (pintype "passive"))
      (node (ref "U26") (pin "3") (pinfunction "A_3") (pintype "passive"))
    )
    (net (code "42") (name "Net-(U26-B)") (class "Default")
      (node (ref "U26") (pin "4") (pinfunction "B_4") (pintype "passive"))
      (node (ref "U36") (pin "3") (pinfunction "A_3") (pintype "passive"))
      (node (ref "U5") (pin "3") (pinfunction "IN3_3") (pintype "input"))
    )
    (net (code "43") (name "Net-(U27-A)") (class "Default")
      (node (ref "R10") (pin "2") (pinfunction "2_2") (pintype "passive"))
      (node (ref "R9") (pin "2") (pinfunction "2_2") (pintype "passive"))
      (node (ref "U27") (pin "3") (pinfunction "A_3") (pintype "passive"))
    )
    (net (code "44") (name "Net-(U28-ADJ)") (class "Default")
      (node (ref "C278") (pin "1") (pinfunction "1_1") (pintype "passive"))
      (node (ref "R5") (pin "2") (pinfunction "2_2") (pintype "passive"))
      (node (ref "R8") (pin "1") (pinfunction "1_1") (pintype "passive"))
      (node (ref "U28") (pin "1") (pinfunction "ADJ_1") (pintype "passive"))
    )
    (net (code "45") (name "Net-(U36-B)") (class "Default")
      (node (ref "C296") (pin "2") (pinfunction "2_2") (pintype "passive"))
      (node (ref "R154") (pin "1") (pinfunction "1_1") (pintype "passive"))
      (node (ref "R155") (pin "1") (pinfunction "1_1") (pintype "passive"))
      (node (ref "U36") (pin "4") (pinfunction "B_4") (pintype "passive"))
    )
    (net (code "46") (name "Net-(U37-B)") (class "Default")
      (node (ref "R122") (pin "1") (pinfunction "1_1") (pintype "passive"))
      (node (ref "R123") (pin "1") (pinfunction "1_1") (pintype "passive"))
      (node (ref "R124") (pin "2") (pinfunction "2_2") (pintype "passive"))
      (node (ref "U37") (pin "4") (pinfunction "B_4") (pintype "passive"))
    )
    (net (code "47") (name "unconnected-(U4-GPIO2-Pad19)") (class "Default")
      (node (ref "U4") (pin "19") (pinfunction "GPIO2_19") (pintype "passive+no_connect"))
    )
    (net (code "48") (name "unconnected-(U4-GPIO3-Pad18)") (class "Default")
      (node (ref "U4") (pin "18") (pinfunction "GPIO3_18") (pintype "passive+no_connect"))
    )
    (net (code "49") (name "unconnected-(U4-GPIO7-Pad17)") (class "Default")
      (node (ref "U4") (pin "17") (pinfunction "GPIO7_17") (pintype "passive+no_connect"))
    )
    (net (code "50") (name "unconnected-(U4-GPIO8-Pad20)") (class "Default")
      (node (ref "U4") (pin "20") (pinfunction "GPIO8_20") (pintype "passive+no_connect"))
    )
    (net (code "51") (name "unconnected-(U4-NC-Pad3)") (class "Default")
      (node (ref "U4") (pin "3") (pinfunction "NC_3") (pintype "passive+no_connect"))
    )
    (net (code "52") (name "unconnected-(U4-RXD1-Pad11)") (class "Default")
      (node (ref "U4") (pin "11") (pinfunction "RXD1_11") (pintype "input+no_connect"))
    )
    (net (code "53") (name "unconnected-(U4-TXD1-Pad10)") (class "Default")
      (node (ref "U4") (pin "10") (pinfunction "TXD1_10") (pintype "output+no_connect"))
    )
    (net (code "54") (name "unconnected-(U4-~{RST}-Pad16)") (class "Default")
      (node (ref "U4") (pin "16") (pinfunction "~{RST}_16") (pintype "passive+no_connect"))
    )
    (net (code "55") (name "unconnected-(U5-CLK3A-Pad10)") (class "Default")
      (node (ref "U5") (pin "10") (pinfunction "CLK3A_10") (pintype "output"))
    )
    (net (code "56") (name "unconnected-(U5-CLK3B-Pad9)") (class "Default")
      (node (ref "U5") (pin "9") (pinfunction "CLK3B_9") (pintype "output"))
    )
    (net (code "57") (name "unconnected-(U5-IN1-Pad1)") (class "Default")
      (node (ref "U5") (pin "1") (pinfunction "IN1_1") (pintype "input+no_connect"))
    )
  )
)
